# Ex_Controller_ExPwr.net
KiCad netlist of a schematic drawn in EAGLE
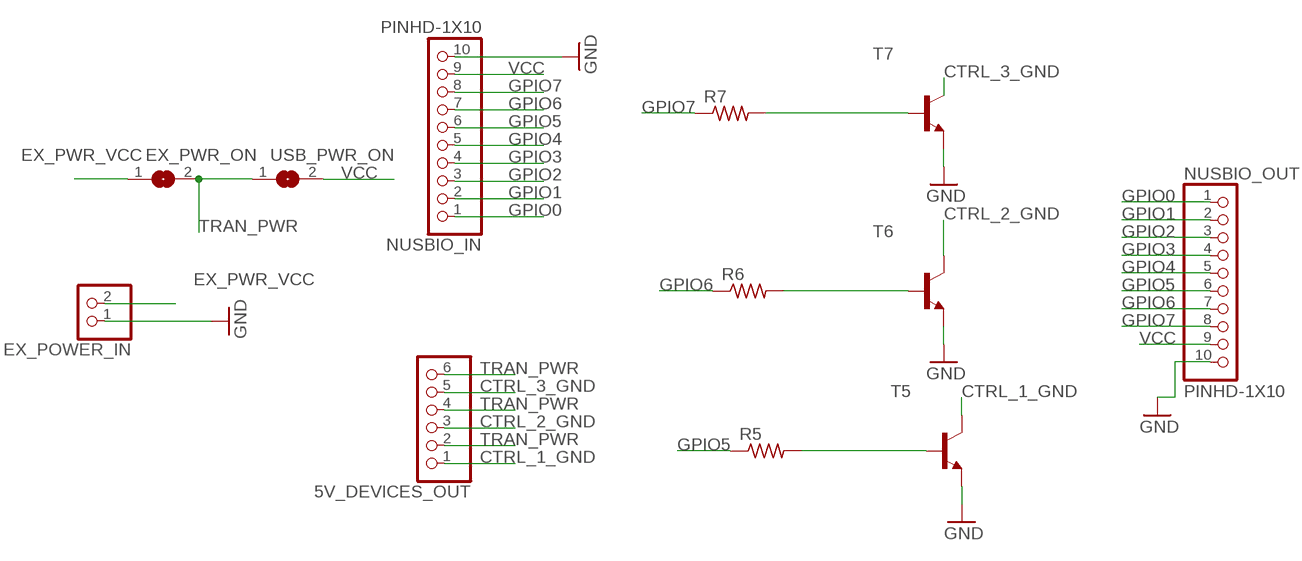
[diagram p0: schematic, sheet 1]

(export (version "E")
  (design (tool "Eeschema 10.0.6"))
  (components
    (comp (ref "5V_DEVICES_OUT")
      (value "PINHD-1X6")
      (footprint "eagle-import:1X06")
      (libsource (lib "eagle-import") (part "PINHD-1X6"))
    )
    (comp (ref "EX_POWER_IN")
      (value "PINHD-1X2")
      (footprint "eagle-import:1X02")
      (libsource (lib "eagle-import") (part "PINHD-1X2"))
    )
    (comp (ref "EX_PWR_ON")
      (value "SOLDERJUMPERREFLOW")
      (footprint "eagle-import:SOLDERJUMPER_REFLOW")
      (libsource (lib "eagle-import") (part "SOLDERJUMPERREFLOW"))
    )
    (comp (ref "NUSBIO_IN")
      (value "PINHD-1X10")
      (footprint "eagle-import:1X10-BIG")
      (libsource (lib "eagle-import") (part "PINHD-1X10"))
    )
    (comp (ref "NUSBIO_OUT")
      (value "PINHD-1X10")
      (footprint "eagle-import:1X10-BIG")
      (libsource (lib "eagle-import") (part "PINHD-1X10"))
    )
    (comp (ref "R5")
      (value "R-US_R0805")
      (footprint "eagle-import:R0805")
      (libsource (lib "eagle-import") (part "R-US_R0805"))
    )
    (comp (ref "R6")
      (value "R-US_R0805")
      (footprint "eagle-import:R0805")
      (libsource (lib "eagle-import") (part "R-US_R0805"))
    )
    (comp (ref "R7")
      (value "R-US_R0805")
      (footprint "eagle-import:R0805")
      (libsource (lib "eagle-import") (part "R-US_R0805"))
    )
    (comp (ref "T5")
      (value "MMBT3904LT1-NPN-SOT23-BEC")
      (footprint "eagle-import:SOT23-BEC")
      (libsource (lib "eagle-import") (part "-NPN-SOT23-BECMMBT3904LT1"))
    )
    (comp (ref "T6")
      (value "MMBT3904LT1-NPN-SOT23-BEC")
      (footprint "eagle-import:SOT23-BEC")
      (libsource (lib "eagle-import") (part "-NPN-SOT23-BECMMBT3904LT1"))
    )
    (comp (ref "T7")
      (value "MMBT3904LT1-NPN-SOT23-BEC")
      (footprint "eagle-import:SOT23-BEC")
      (libsource (lib "eagle-import") (part "-NPN-SOT23-BECMMBT3904LT1"))
    )
    (comp (ref "USB_PWR_ON")
      (value "SOLDERJUMPERREFLOW")
      (footprint "eagle-import:SOLDERJUMPER_REFLOW")
      (libsource (lib "eagle-import") (part "SOLDERJUMPERREFLOW"))
    )
  )
  (nets
    (net (code "1") (name "/CTRL_1_GND") (class "Default")
      (node (ref "5V_DEVICES_OUT") (pin "1") (pinfunction "1_1") (pintype "passive"))
      (node (ref "T5") (pin "C") (pinfunction "C_C") (pintype "passive"))
    )
    (net (code "2") (name "/CTRL_2_GND") (class "Default")
      (node (ref "5V_DEVICES_OUT") (pin "3") (pinfunction "3_3") (pintype "passive"))
      (node (ref "T6") (pin "C") (pinfunction "C_C") (pintype "passive"))
    )
    (net (code "3") (name "/CTRL_3_GND") (class "Default")
      (node (ref "5V_DEVICES_OUT") (pin "5") (pinfunction "5_5") (pintype "passive"))
      (node (ref "T7") (pin "C") (pinfunction "C_C") (pintype "passive"))
    )
    (net (code "4") (name "/EX_PWR_VCC") (class "Default")
      (node (ref "EX_POWER_IN") (pin "2") (pinfunction "2_2") (pintype "passive"))
      (node (ref "EX_PWR_ON") (pin "1") (pinfunction "1_1") (pintype "passive"))
    )
    (net (code "5") (name "/GPIO0") (class "Default")
      (node (ref "NUSBIO_IN") (pin "1") (pinfunction "1_1") (pintype "passive"))
      (node (ref "NUSBIO_OUT") (pin "1") (pinfunction "1_1") (pintype "passive"))
    )
    (net (code "6") (name "/GPIO1") (class "Default")
      (node (ref "NUSBIO_IN") (pin "2") (pinfunction "2_2") (pintype "passive"))
      (node (ref "NUSBIO_OUT") (pin "2") (pinfunction "2_2") (pintype "passive"))
    )
    (net (code "7") (name "/GPIO2") (class "Default")
      (node (ref "NUSBIO_IN") (pin "3") (pinfunction "3_3") (pintype "passive"))
      (node (ref "NUSBIO_OUT") (pin "3") (pinfunction "3_3") (pintype "passive"))
    )
    (net (code "8") (name "/GPIO3") (class "Default")
      (node (ref "NUSBIO_IN") (pin "4") (pinfunction "4_4") (pintype "passive"))
      (node (ref "NUSBIO_OUT") (pin "4") (pinfunction "4_4") (pintype "passive"))
    )
    (net (code "9") (name "/GPIO4") (class "Default")
      (node (ref "NUSBIO_IN") (pin "5") (pinfunction "5_5") (pintype "passive"))
      (node (ref "NUSBIO_OUT") (pin "5") (pinfunction "5_5") (pintype "passive"))
    )
    (net (code "10") (name "/GPIO5") (class "Default")
      (node (ref "NUSBIO_IN") (pin "6") (pinfunction "6_6") (pintype "passive"))
      (node (ref "NUSBIO_OUT") (pin "6") (pinfunction "6_6") (pintype "passive"))
      (node (ref "R5") (pin "1") (pinfunction "1_1") (pintype "passive"))
    )
    (net (code "11") (name "/GPIO6") (class "Default")
      (node (ref "NUSBIO_IN") (pin "7") (pinfunction "7_7") (pintype "passive"))
      (node (ref "NUSBIO_OUT") (pin "7") (pinfunction "7_7") (pintype "passive"))
      (node (ref "R6") (pin "1") (pinfunction "1_1") (pintype "passive"))
    )
    (net (code "12") (name "/GPIO7") (class "Default")
      (node (ref "NUSBIO_IN") (pin "8") (pinfunction "8_8") (pintype "passive"))
      (node (ref "NUSBIO_OUT") (pin "8") (pinfunction "8_8") (pintype "passive"))
      (node (ref "R7") (pin "1") (pinfunction "1_1") (pintype "passive"))
    )
    (net (code "13") (name "/TRAN_PWR") (class "Default")
      (node (ref "5V_DEVICES_OUT") (pin "2") (pinfunction "2_2") (pintype "passive"))
      (node (ref "5V_DEVICES_OUT") (pin "4") (pinfunction "4_4") (pintype "passive"))
      (node (ref "5V_DEVICES_OUT") (pin "6") (pinfunction "6_6") (pintype "passive"))
      (node (ref "EX_PWR_ON") (pin "2") (pinfunction "2_2") (pintype "passive"))
      (node (ref "USB_PWR_ON") (pin "1") (pinfunction "1_1") (pintype "passive"))
    )
    (net (code "14") (name "/VCC") (class "Default")
      (node (ref "NUSBIO_IN") (pin "9") (pinfunction "9_9") (pintype "passive"))
      (node (ref "NUSBIO_OUT") (pin "9") (pinfunction "9_9") (pintype "passive"))
      (node (ref "USB_PWR_ON") (pin "2") (pinfunction "2_2") (pintype "passive"))
    )
    (net (code "15") (name "GND") (class "Default")
      (node (ref "EX_POWER_IN") (pin "1") (pinfunction "1_1") (pintype "passive"))
      (node (ref "NUSBIO_IN") (pin "10") (pinfunction "10_10") (pintype "passive"))
      (node (ref "NUSBIO_OUT") (pin "10") (pinfunction "10_10") (pintype "passive"))
      (node (ref "T5") (pin "E") (pinfunction "E_E") (pintype "passive"))
      (node (ref "T6") (pin "E") (pinfunction "E_E") (pintype "passive"))
      (node (ref "T7") (pin "E") (pinfunction "E_E") (pintype "passive"))
    )
    (net (code "16") (name "Net-(R5-Pad2)") (class "Default")
      (node (ref "R5") (pin "2") (pinfunction "2_2") (pintype "passive"))
      (node (ref "T5") (pin "B") (pinfunction "B_B") (pintype "passive"))
    )
    (net (code "17") (name "Net-(R6-Pad2)") (class "Default")
      (node (ref "R6") (pin "2") (pinfunction "2_2") (pintype "passive"))
      (node (ref "T6") (pin "B") (pinfunction "B_B") (pintype "passive"))
    )
    (net (code "18") (name "Net-(R7-Pad2)") (class "Default")
      (node (ref "R7") (pin "2") (pinfunction "2_2") (pintype "passive"))
      (node (ref "T7") (pin "B") (pinfunction "B_B") (pintype "passive"))
    )
  )
)
